# jtagio.net
KiCad netlist of a schematic drawn in Altium Designer
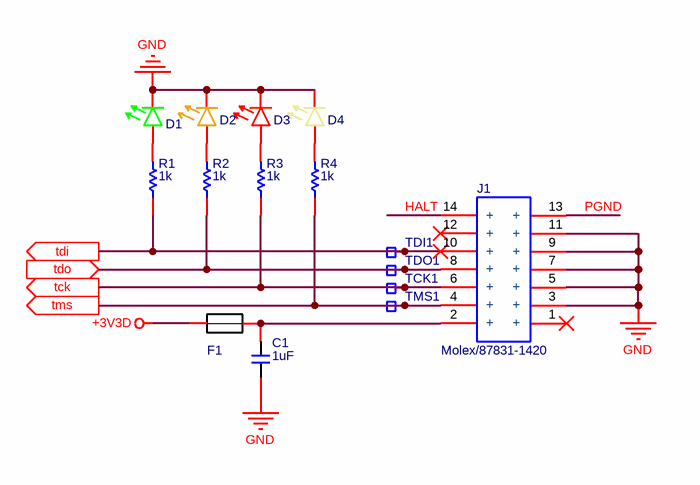
[diagram p0: jtagio.SchDoc]

(export (version "E")
  (design (tool "Eeschema 10.0.6"))
  (components
    (comp (ref "C1")
      (value "1uF")
      (footprint "C0603")
      (description "CAP-CER, 2, 1.0uF, 10%, 25V, 0603")
      (fields
        (field (name "MANUFACTURER") "Murata Electronics North America")
        (field (name "MANUFACTURER PART NUMBER") "GRM188R61E105KA12D")
      )
      (libsource (lib "stdlib") (part "Murata/GRM188R61E105KA12D"))
    )
    (comp (ref "D1")
      (value "LITEON/LTST-C191KGKT")
      (footprint "LED0603")
      (description "LED, 20mA, 0603, Green")
      (libsource (lib "stdlib") (part "LITEON/LTST-C191KGKT"))
    )
    (comp (ref "D2")
      (value "Vishay/TLMO1000-GS08")
      (footprint "LED0603")
      (description "LED, 2mA, 0603, Soft Orange")
      (fields
        (field (name "MANUFACTURER") "Vishay Semiconductor Opto Division")
        (field (name "MANUFACTURER PART NUMBER") "TLMO1000-GS08")
      )
      (libsource (lib "stdlib") (part "Vishay/TLMO1000-GS08"))
    )
    (comp (ref "D3")
      (value "Vishay/TLMS1000-GS08")
      (footprint "LED0603")
      (description "LED, 2mA, 0603, Red")
      (fields
        (field (name "MANUFACTURER") "Vishay Semiconductor Opto Division")
        (field (name "MANUFACTURER PART NUMBER") "TLMS1000-GS08")
      )
      (libsource (lib "stdlib") (part "Vishay/TLMS1000-GS08"))
    )
    (comp (ref "D4")
      (value "Vishay/TLMY1000-GS08")
      (footprint "LED0603")
      (description "LED, 2mA, 0603, Yellow")
      (fields
        (field (name "MANUFACTURER") "Vishay Semiconductor Opto Division")
        (field (name "MANUFACTURER PART NUMBER") "TLMY1000-GS08")
      )
      (libsource (lib "stdlib") (part "Vishay/TLMY1000-GS08"))
    )
    (comp (ref "F1")
      (value "Littelfuse/1206L")
      (footprint "R1206")
      (description "FUSE, Resetable, 1206 Generic")
      (libsource (lib "stdlib") (part "Littelfuse/1206L"))
    )
    (comp (ref "J1")
      (value "Molex/87831-1420")
      (footprint "Molex Milligrid 7x2")
      (description "Header 8x2 2.0mm")
      (fields
        (field (name "MANUFACTURER") "Molex, LLC")
        (field (name "MANUFACTURER PART NUMBER") "0878311420")
      )
      (libsource (lib "stdlib") (part "Molex/87831-1420"))
    )
    (comp (ref "R1")
      (value "1k")
      (footprint "R0603")
      (description "RES1, SMD, 1.00k, 1.0%, 1/10W, 0603")
      (fields
        (field (name "MANUFACTURER") "Vishay Dale")
        (field (name "MANUFACTURER PART NUMBER") "CRCW06031K00FKEA")
      )
      (libsource (lib "stdlib") (part "CRCW06031K00FKEA"))
    )
    (comp (ref "R2")
      (value "1k")
      (footprint "R0603")
      (description "RES1, SMD, 1.00k, 1.0%, 1/10W, 0603")
      (fields
        (field (name "MANUFACTURER") "Vishay Dale")
        (field (name "MANUFACTURER PART NUMBER") "CRCW06031K00FKEA")
      )
      (libsource (lib "stdlib") (part "CRCW06031K00FKEA"))
    )
    (comp (ref "R3")
      (value "1k")
      (footprint "R0603")
      (description "RES1, SMD, 1.00k, 1.0%, 1/10W, 0603")
      (fields
        (field (name "MANUFACTURER") "Vishay Dale")
        (field (name "MANUFACTURER PART NUMBER") "CRCW06031K00FKEA")
      )
      (libsource (lib "stdlib") (part "CRCW06031K00FKEA"))
    )
    (comp (ref "R4")
      (value "1k")
      (footprint "R0603")
      (description "RES1, SMD, 1.00k, 1.0%, 1/10W, 0603")
      (fields
        (field (name "MANUFACTURER") "Vishay Dale")
        (field (name "MANUFACTURER PART NUMBER") "CRCW06031K00FKEA")
      )
      (libsource (lib "stdlib") (part "CRCW06031K00FKEA"))
    )
    (comp (ref "TCK1")
      (value "TP")
      (footprint "TP")
      (description "Test Point, Generic, 100MIL")
      (libsource (lib "stdlib") (part "TP"))
    )
    (comp (ref "TDI1")
      (value "TP")
      (footprint "TP")
      (description "Test Point, Generic, 100MIL")
      (libsource (lib "stdlib") (part "TP"))
    )
    (comp (ref "TDO1")
      (value "TP")
      (footprint "TP")
      (description "Test Point, Generic, 100MIL")
      (libsource (lib "stdlib") (part "TP"))
    )
    (comp (ref "TMS1")
      (value "TP")
      (footprint "TP")
      (description "Test Point, Generic, 100MIL")
      (libsource (lib "stdlib") (part "TP"))
    )
  )
  (nets
    (net (code "1") (name "+3V3D") (class "Default")
      (node (ref "F1") (pin "1") (pinfunction "0_1") (pintype "passive"))
    )
    (net (code "2") (name "/HALT") (class "Default")
      (node (ref "J1") (pin "14") (pinfunction "+_14") (pintype "passive"))
    )
    (net (code "3") (name "/PGND") (class "Default")
      (node (ref "J1") (pin "13") (pinfunction "+_13") (pintype "passive"))
    )
    (net (code "4") (name "/tck") (class "Default")
      (node (ref "J1") (pin "6") (pinfunction "+_6") (pintype "passive"))
      (node (ref "R3") (pin "1") (pinfunction "1_1") (pintype "passive"))
      (node (ref "TCK1") (pin "1") (pinfunction "1_1") (pintype "passive"))
    )
    (net (code "5") (name "/tdi") (class "Default")
      (node (ref "J1") (pin "10") (pinfunction "+_10") (pintype "passive"))
      (node (ref "R1") (pin "1") (pinfunction "1_1") (pintype "passive"))
      (node (ref "TDI1") (pin "1") (pinfunction "1_1") (pintype "passive"))
    )
    (net (code "6") (name "/tdo") (class "Default")
      (node (ref "J1") (pin "8") (pinfunction "+_8") (pintype "passive"))
      (node (ref "R2") (pin "1") (pinfunction "1_1") (pintype "passive"))
      (node (ref "TDO1") (pin "1") (pinfunction "1_1") (pintype "passive"))
    )
    (net (code "7") (name "/tms") (class "Default")
      (node (ref "J1") (pin "4") (pinfunction "+_4") (pintype "passive"))
      (node (ref "R4") (pin "1") (pinfunction "1_1") (pintype "passive"))
      (node (ref "TMS1") (pin "1") (pinfunction "1_1") (pintype "passive"))
    )
    (net (code "8") (name "GND") (class "Default")
      (node (ref "C1") (pin "2") (pinfunction "2_2") (pintype "passive"))
      (node (ref "D1") (pin "C") (pintype "passive"))
      (node (ref "D2") (pin "C") (pintype "passive"))
      (node (ref "D3") (pin "C") (pintype "passive"))
      (node (ref "D4") (pin "C") (pintype "passive"))
      (node (ref "J1") (pin "11") (pinfunction "+_11") (pintype "passive"))
      (node (ref "J1") (pin "3") (pinfunction "+_3") (pintype "passive"))
      (node (ref "J1") (pin "5") (pinfunction "+_5") (pintype "passive"))
      (node (ref "J1") (pin "7") (pinfunction "+_7") (pintype "passive"))
      (node (ref "J1") (pin "9") (pinfunction "+_9") (pintype "passive"))
    )
    (net (code "9") (name "Net-(C1-5)") (class "Default")
      (node (ref "C1") (pin "1") (pinfunction "5_1") (pintype "passive"))
      (node (ref "F1") (pin "2") (pinfunction "2_2") (pintype "passive"))
      (node (ref "J1") (pin "2") (pinfunction "+_2") (pintype "passive"))
    )
    (net (code "10") (name "Net-(D1-PadA)") (class "Default")
      (node (ref "D1") (pin "A") (pintype "passive"))
      (node (ref "R1") (pin "2") (pinfunction "2_2") (pintype "passive"))
    )
    (net (code "11") (name "Net-(D2-PadA)") (class "Default")
      (node (ref "D2") (pin "A") (pintype "passive"))
      (node (ref "R2") (pin "2") (pinfunction "2_2") (pintype "passive"))
    )
    (net (code "12") (name "Net-(D3-PadA)") (class "Default")
      (node (ref "D3") (pin "A") (pintype "passive"))
      (node (ref "R3") (pin "2") (pinfunction "2_2") (pintype "passive"))
    )
    (net (code "13") (name "Net-(D4-PadA)") (class "Default")
      (node (ref "D4") (pin "A") (pintype "passive"))
      (node (ref "R4") (pin "2") (pinfunction "2_2") (pintype "passive"))
    )
    (net (code "14") (name "unconnected-(J1-+-Pad1)") (class "Default")
      (node (ref "J1") (pin "1") (pinfunction "+_1") (pintype "passive+no_connect"))
    )
    (net (code "15") (name "unconnected-(J1-+-Pad12)") (class "Default")
      (node (ref "J1") (pin "12") (pinfunction "+_12") (pintype "passive+no_connect"))
    )
  )
)
